# gm328a.net
KiCad netlist of a schematic drawn in EAGLE
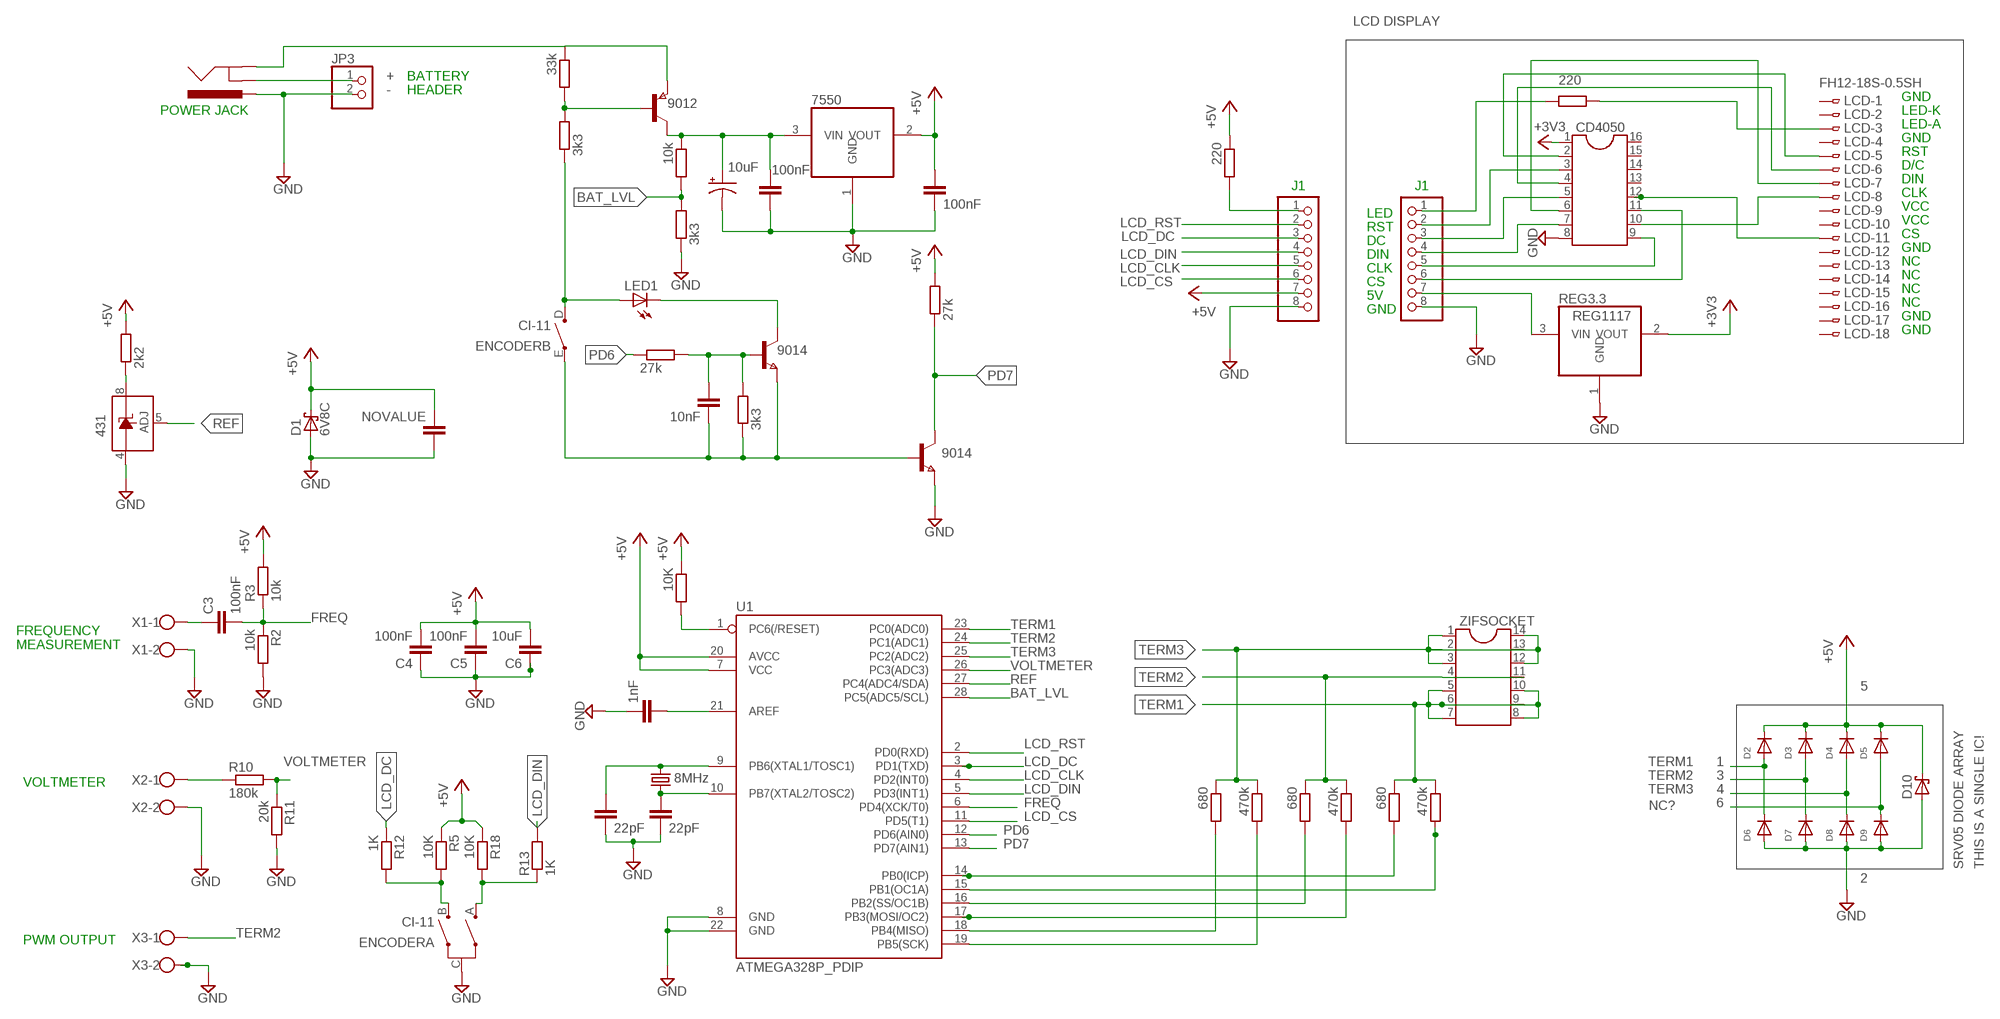
[diagram p0: schematic, sheet 1]

(export (version "E")
  (design (tool "Eeschema 10.0.6"))
  (components
    (comp (ref "1")
      (value "9014")
      (footprint "eagle-import:SOT323")
      (fields (field (name "MPN") "DSS4160U-7"))
      (libsource (lib "eagle-import") (part "NPNSOT323"))
    )
    (comp (ref "10K6")
      (value "10K")
      (footprint "eagle-import:M0805")
      (libsource (lib "eagle-import") (part "R-EU_M0805"))
    )
    (comp (ref "7550")
      (value "REG1117")
      (footprint "eagle-import:SOT223")
      (libsource (lib "eagle-import") (part "REG1117"))
    )
    (comp (ref "9012")
      (value "PNPSOT323")
      (footprint "eagle-import:SOT323")
      (fields (field (name "MPN") "2DB1689-7"))
      (libsource (lib "eagle-import") (part "PNPSOT323"))
    )
    (comp (ref "9014")
      (value "NPNSOT323")
      (footprint "eagle-import:SOT323")
      (fields (field (name "MPN") "DSS4160U-7"))
      (libsource (lib "eagle-import") (part "NPNSOT323"))
    )
    (comp (ref "C1")
      (value "22pF")
      (footprint "eagle-import:C0805")
      (libsource (lib "eagle-import") (part "C-EUC0805"))
    )
    (comp (ref "C2")
      (value "22pF")
      (footprint "eagle-import:C0805")
      (libsource (lib "eagle-import") (part "C-EUC0805"))
    )
    (comp (ref "C3")
      (value "100nF")
      (footprint "eagle-import:C0805")
      (libsource (lib "eagle-import") (part "C-EUC0805"))
    )
    (comp (ref "C4")
      (value "100nF")
      (footprint "eagle-import:C0805")
      (libsource (lib "eagle-import") (part "C-EUC0805"))
    )
    (comp (ref "C5")
      (value "100nF")
      (footprint "eagle-import:C0805")
      (libsource (lib "eagle-import") (part "C-EUC0805"))
    )
    (comp (ref "C6")
      (value "10uF")
      (footprint "eagle-import:C0805")
      (libsource (lib "eagle-import") (part "C-EUC0805"))
    )
    (comp (ref "C7")
      (value "100nF")
      (footprint "eagle-import:C0805")
      (libsource (lib "eagle-import") (part "C-EUC0805"))
    )
    (comp (ref "C8")
      (value "10uF")
      (footprint "eagle-import:PANASONIC_C")
      (libsource (lib "eagle-import") (part "CPOL-USC"))
    )
    (comp (ref "C9")
      (value "100nF")
      (footprint "eagle-import:C0805")
      (libsource (lib "eagle-import") (part "C-EUC0805"))
    )
    (comp (ref "C10")
      (value "10nF")
      (footprint "eagle-import:C0805")
      (libsource (lib "eagle-import") (part "C-EUC0805"))
    )
    (comp (ref "C11")
      (value "1nF")
      (footprint "eagle-import:C0805")
      (libsource (lib "eagle-import") (part "C-EUC0805"))
    )
    (comp (ref "C12")
      (value "NOVALUE")
      (footprint "eagle-import:C0805")
      (libsource (lib "eagle-import") (part "C-EUC0805"))
    )
    (comp (ref "CD4050")
      (value "DIL16")
      (footprint "eagle-import:DIL16")
      (libsource (lib "eagle-import") (part "DIL16"))
    )
    (comp (ref "D1")
      (value "6V8C")
      (footprint "eagle-import:DO41-10")
      (libsource (lib "eagle-import") (part "P4KEXX"))
    )
    (comp (ref "D2")
      (value "DIODE_SOD-123FL")
      (footprint "eagle-import:SOD-123FL")
      (libsource (lib "eagle-import") (part "DIODE_SOD-123FL"))
    )
    (comp (ref "D3")
      (value "DIODE_SOD-123FL")
      (footprint "eagle-import:SOD-123FL")
      (libsource (lib "eagle-import") (part "DIODE_SOD-123FL"))
    )
    (comp (ref "D4")
      (value "DIODE_SOD-123FL")
      (footprint "eagle-import:SOD-123FL")
      (libsource (lib "eagle-import") (part "DIODE_SOD-123FL"))
    )
    (comp (ref "D5")
      (value "DIODE_SOD-123FL")
      (footprint "eagle-import:SOD-123FL")
      (libsource (lib "eagle-import") (part "DIODE_SOD-123FL"))
    )
    (comp (ref "D6")
      (value "DIODE_SOD-123FL")
      (footprint "eagle-import:SOD-123FL")
      (libsource (lib "eagle-import") (part "DIODE_SOD-123FL"))
    )
    (comp (ref "D7")
      (value "DIODE_SOD-123FL")
      (footprint "eagle-import:SOD-123FL")
      (libsource (lib "eagle-import") (part "DIODE_SOD-123FL"))
    )
    (comp (ref "D8")
      (value "DIODE_SOD-123FL")
      (footprint "eagle-import:SOD-123FL")
      (libsource (lib "eagle-import") (part "DIODE_SOD-123FL"))
    )
    (comp (ref "D9")
      (value "DIODE_SOD-123FL")
      (footprint "eagle-import:SOD-123FL")
      (libsource (lib "eagle-import") (part "DIODE_SOD-123FL"))
    )
    (comp (ref "D10")
      (value "P4KEXX")
      (footprint "eagle-import:DO41-10")
      (libsource (lib "eagle-import") (part "P4KEXX"))
    )
    (comp (ref "ENCODER")
      (value "CI-11")
      (footprint "eagle-import:CI-11")
      (libsource (lib "eagle-import") (part "CI-11"))
    )
    (comp (ref "IC1")
      (value "LM336D")
      (footprint "eagle-import:SO08")
      (libsource (lib "eagle-import") (part "LM336D"))
    )
    (comp (ref "J1")
      (value "POWER_JACKSLT")
      (footprint "eagle-import:POWER_JACK_SLOT")
      (libsource (lib "eagle-import") (part "POWER_JACKSLT"))
    )
    (comp (ref "JP1")
      (value "PINHD-1X8")
      (footprint "eagle-import:1X08")
      (libsource (lib "eagle-import") (part "PINHD-1X8"))
    )
    (comp (ref "JP2")
      (value "PINHD-1X8")
      (footprint "eagle-import:1X08")
      (libsource (lib "eagle-import") (part "PINHD-1X8"))
    )
    (comp (ref "JP3")
      (value "PINHD-1X2")
      (footprint "eagle-import:1X02")
      (libsource (lib "eagle-import") (part "PINHD-1X2"))
    )
    (comp (ref "LCD")
      (value "FH12-18S-0.5SH")
      (footprint "eagle-import:FH12-18S-0.5SH")
      (fields (field (name "MPN") "FH12-18S-0.5SH(55)"))
      (libsource (lib "eagle-import") (part "FH12-18S-0.5SH"))
    )
    (comp (ref "LED1")
      (value "LEDSML0805")
      (footprint "eagle-import:SML0805")
      (libsource (lib "eagle-import") (part "LEDSML0805"))
    )
    (comp (ref "Q1")
      (value "8MHz")
      (footprint "eagle-import:HC49_S")
      (libsource (lib "eagle-import") (part "CRYSTALHC49S"))
    )
    (comp (ref "R1")
      (value "220")
      (footprint "eagle-import:M0805")
      (libsource (lib "eagle-import") (part "R-EU_M0805"))
    )
    (comp (ref "R2")
      (value "10k")
      (footprint "eagle-import:M0805")
      (libsource (lib "eagle-import") (part "R-EU_M0805"))
    )
    (comp (ref "R3")
      (value "10k")
      (footprint "eagle-import:M0805")
      (libsource (lib "eagle-import") (part "R-EU_M0805"))
    )
    (comp (ref "R4")
      (value "220")
      (footprint "eagle-import:M0805")
      (libsource (lib "eagle-import") (part "R-EU_M0805"))
    )
    (comp (ref "R5")
      (value "10K")
      (footprint "eagle-import:M0805")
      (libsource (lib "eagle-import") (part "R-EU_M0805"))
    )
    (comp (ref "R6")
      (value "33k")
      (footprint "eagle-import:M0805")
      (libsource (lib "eagle-import") (part "R-EU_M0805"))
    )
    (comp (ref "R7")
      (value "3k3")
      (footprint "eagle-import:M0805")
      (libsource (lib "eagle-import") (part "R-EU_M0805"))
    )
    (comp (ref "R8")
      (value "3k3")
      (footprint "eagle-import:M0805")
      (libsource (lib "eagle-import") (part "R-EU_M0805"))
    )
    (comp (ref "R9")
      (value "10k")
      (footprint "eagle-import:M0805")
      (libsource (lib "eagle-import") (part "R-EU_M0805"))
    )
    (comp (ref "R10")
      (value "180k")
      (footprint "eagle-import:M0805")
      (libsource (lib "eagle-import") (part "R-EU_M0805"))
    )
    (comp (ref "R11")
      (value "20k")
      (footprint "eagle-import:M0805")
      (libsource (lib "eagle-import") (part "R-EU_M0805"))
    )
    (comp (ref "R12")
      (value "1K")
      (footprint "eagle-import:M0805")
      (libsource (lib "eagle-import") (part "R-EU_M0805"))
    )
    (comp (ref "R13")
      (value "1K")
      (footprint "eagle-import:M0805")
      (libsource (lib "eagle-import") (part "R-EU_M0805"))
    )
    (comp (ref "R14")
      (value "2k2")
      (footprint "eagle-import:M0805")
      (libsource (lib "eagle-import") (part "R-EU_M0805"))
    )
    (comp (ref "R15")
      (value "27k")
      (footprint "eagle-import:M0805")
      (libsource (lib "eagle-import") (part "R-EU_M0805"))
    )
    (comp (ref "R16")
      (value "3k3")
      (footprint "eagle-import:M0805")
      (libsource (lib "eagle-import") (part "R-EU_M0805"))
    )
    (comp (ref "R17")
      (value "27k")
      (footprint "eagle-import:M0805")
      (libsource (lib "eagle-import") (part "R-EU_M0805"))
    )
    (comp (ref "R18")
      (value "10K")
      (footprint "eagle-import:M0805")
      (libsource (lib "eagle-import") (part "R-EU_M0805"))
    )
    (comp (ref "R19")
      (value "680")
      (footprint "eagle-import:M0805")
      (libsource (lib "eagle-import") (part "R-EU_M0805"))
    )
    (comp (ref "R20")
      (value "470k")
      (footprint "eagle-import:M0805")
      (libsource (lib "eagle-import") (part "R-EU_M0805"))
    )
    (comp (ref "R21")
      (value "680")
      (footprint "eagle-import:M0805")
      (libsource (lib "eagle-import") (part "R-EU_M0805"))
    )
    (comp (ref "R22")
      (value "470k")
      (footprint "eagle-import:M0805")
      (libsource (lib "eagle-import") (part "R-EU_M0805"))
    )
    (comp (ref "R23")
      (value "680")
      (footprint "eagle-import:M0805")
      (libsource (lib "eagle-import") (part "R-EU_M0805"))
    )
    (comp (ref "R24")
      (value "470k")
      (footprint "eagle-import:M0805")
      (libsource (lib "eagle-import") (part "R-EU_M0805"))
    )
    (comp (ref "REG3.3")
      (value "REG1117")
      (footprint "eagle-import:SOT223")
      (libsource (lib "eagle-import") (part "REG1117"))
    )
    (comp (ref "U1")
      (value "ATMEGA328P_PDIP")
      (footprint "eagle-import:DIL28-3")
      (libsource (lib "eagle-import") (part "ATMEGA328P_PDIP"))
    )
    (comp (ref "X1")
      (value "W237-102")
      (footprint "eagle-import:W237-102")
      (fields (field (name "MPN") "237-102"))
      (libsource (lib "eagle-import") (part "W237-102"))
    )
    (comp (ref "X2")
      (value "W237-102")
      (footprint "eagle-import:W237-102")
      (fields (field (name "MPN") "237-102"))
      (libsource (lib "eagle-import") (part "W237-102"))
    )
    (comp (ref "X3")
      (value "W237-102")
      (footprint "eagle-import:W237-102")
      (fields (field (name "MPN") "237-102"))
      (libsource (lib "eagle-import") (part "W237-102"))
    )
    (comp (ref "ZIFSOCKET")
      (value "DIL14S")
      (footprint "eagle-import:SOCKET-14")
      (libsource (lib "eagle-import") (part "DIL14S"))
    )
  )
  (nets
    (net (code "1") (name "+3V3") (class "Default")
      (node (ref "CD4050") (pin "1") (pinfunction "1_1") (pintype "passive"))
      (node (ref "REG3.3") (pin "2") (pinfunction "VOUT_2") (pintype "output"))
    )
    (net (code "2") (name "+5V") (class "Default")
      (node (ref "10K6") (pin "1") (pinfunction "1_1") (pintype "passive"))
      (node (ref "7550") (pin "2") (pinfunction "VOUT_2") (pintype "output"))
      (node (ref "C12") (pin "2") (pinfunction "2_2") (pintype "passive"))
      (node (ref "C4") (pin "2") (pinfunction "2_2") (pintype "passive"))
      (node (ref "C5") (pin "2") (pinfunction "2_2") (pintype "passive"))
      (node (ref "C6") (pin "2") (pinfunction "2_2") (pintype "passive"))
      (node (ref "C9") (pin "1") (pinfunction "1_1") (pintype "passive"))
      (node (ref "D1") (pin "C") (pinfunction "C_C") (pintype "passive"))
      (node (ref "D10") (pin "C") (pinfunction "C_C") (pintype "passive"))
      (node (ref "D2") (pin "C") (pinfunction "C_C") (pintype "passive"))
      (node (ref "D3") (pin "C") (pinfunction "C_C") (pintype "passive"))
      (node (ref "D4") (pin "C") (pinfunction "C_C") (pintype "passive"))
      (node (ref "D5") (pin "C") (pinfunction "C_C") (pintype "passive"))
      (node (ref "JP1") (pin "7") (pinfunction "7_7") (pintype "passive"))
      (node (ref "R14") (pin "2") (pinfunction "2_2") (pintype "passive"))
      (node (ref "R17") (pin "2") (pinfunction "2_2") (pintype "passive"))
      (node (ref "R18") (pin "1") (pinfunction "1_1") (pintype "passive"))
      (node (ref "R3") (pin "2") (pinfunction "2_2") (pintype "passive"))
      (node (ref "R4") (pin "1") (pinfunction "1_1") (pintype "passive"))
      (node (ref "R5") (pin "1") (pinfunction "1_1") (pintype "passive"))
      (node (ref "U1") (pin "20") (pinfunction "AVCC_20") (pintype "bidirectional"))
      (node (ref "U1") (pin "7") (pinfunction "VCC_7") (pintype "bidirectional"))
    )
    (net (code "3") (name "/FREQ") (class "Default")
      (node (ref "C3") (pin "2") (pinfunction "2_2") (pintype "passive"))
      (node (ref "R2") (pin "1") (pinfunction "1_1") (pintype "passive"))
      (node (ref "R3") (pin "1") (pinfunction "1_1") (pintype "passive"))
      (node (ref "U1") (pin "6") (pinfunction "PD4(XCK/T0)_6") (pintype "bidirectional"))
    )
    (net (code "4") (name "/LCD_CLK") (class "Default")
      (node (ref "JP1") (pin "5") (pinfunction "5_5") (pintype "passive"))
      (node (ref "U1") (pin "4") (pinfunction "PD2(INT0)_4") (pintype "bidirectional"))
    )
    (net (code "5") (name "/LCD_CS") (class "Default")
      (node (ref "JP1") (pin "6") (pinfunction "6_6") (pintype "passive"))
      (node (ref "U1") (pin "11") (pinfunction "PD5(T1)_11") (pintype "bidirectional"))
    )
    (net (code "6") (name "/LCD_RST") (class "Default")
      (node (ref "JP1") (pin "2") (pinfunction "2_2") (pintype "passive"))
      (node (ref "U1") (pin "2") (pinfunction "PD0(RXD)_2") (pintype "bidirectional"))
    )
    (net (code "7") (name "/NC?") (class "Default")
      (node (ref "D5") (pin "A") (pinfunction "A_A") (pintype "passive"))
      (node (ref "D9") (pin "C") (pinfunction "C_C") (pintype "passive"))
    )
    (net (code "8") (name "/VOLTMETER") (class "Default")
      (node (ref "R10") (pin "2") (pinfunction "2_2") (pintype "passive"))
      (node (ref "R11") (pin "1") (pinfunction "1_1") (pintype "passive"))
      (node (ref "U1") (pin "26") (pinfunction "PC3(ADC3)_26") (pintype "bidirectional"))
    )
    (net (code "9") (name "BAT_LVL") (class "Default")
      (node (ref "R8") (pin "2") (pinfunction "2_2") (pintype "passive"))
      (node (ref "R9") (pin "2") (pinfunction "2_2") (pintype "passive"))
      (node (ref "U1") (pin "28") (pinfunction "PC5(ADC5/SCL)_28") (pintype "bidirectional"))
    )
    (net (code "10") (name "GND") (class "Default")
      (node (ref "7550") (pin "1") (pinfunction "GND_1") (pintype "power_in"))
      (node (ref "9014") (pin "3") (pinfunction "E_3") (pintype "passive"))
      (node (ref "C1") (pin "2") (pinfunction "2_2") (pintype "passive"))
      (node (ref "C11") (pin "1") (pinfunction "1_1") (pintype "passive"))
      (node (ref "C12") (pin "1") (pinfunction "1_1") (pintype "passive"))
      (node (ref "C2") (pin "2") (pinfunction "2_2") (pintype "passive"))
      (node (ref "C4") (pin "1") (pinfunction "1_1") (pintype "passive"))
      (node (ref "C5") (pin "1") (pinfunction "1_1") (pintype "passive"))
      (node (ref "C6") (pin "1") (pinfunction "1_1") (pintype "passive"))
      (node (ref "C7") (pin "2") (pinfunction "2_2") (pintype "passive"))
      (node (ref "C8") (pin "-") (pinfunction "-_-") (pintype "passive"))
      (node (ref "C9") (pin "2") (pinfunction "2_2") (pintype "passive"))
      (node (ref "CD4050") (pin "8") (pinfunction "8_8") (pintype "passive"))
      (node (ref "D1") (pin "A") (pinfunction "A_A") (pintype "passive"))
      (node (ref "D10") (pin "A") (pinfunction "A_A") (pintype "passive"))
      (node (ref "D6") (pin "A") (pinfunction "A_A") (pintype "passive"))
      (node (ref "D7") (pin "A") (pinfunction "A_A") (pintype "passive"))
      (node (ref "D8") (pin "A") (pinfunction "A_A") (pintype "passive"))
      (node (ref "D9") (pin "A") (pinfunction "A_A") (pintype "passive"))
      (node (ref "ENCODER") (pin "C") (pinfunction "C_C") (pintype "passive"))
      (node (ref "IC1") (pin "4") (pinfunction "A_4") (pintype "input"))
      (node (ref "J1") (pin "PWR") (pinfunction "PWR_PWR") (pintype "bidirectional"))
      (node (ref "JP1") (pin "8") (pinfunction "8_8") (pintype "passive"))
      (node (ref "JP2") (pin "8") (pinfunction "8_8") (pintype "passive"))
      (node (ref "JP3") (pin "2") (pinfunction "2_2") (pintype "passive"))
      (node (ref "R11") (pin "2") (pinfunction "2_2") (pintype "passive"))
      (node (ref "R2") (pin "2") (pinfunction "2_2") (pintype "passive"))
      (node (ref "R8") (pin "1") (pinfunction "1_1") (pintype "passive"))
      (node (ref "REG3.3") (pin "1") (pinfunction "GND_1") (pintype "power_in"))
      (node (ref "U1") (pin "22") (pinfunction "GND_22") (pintype "bidirectional"))
      (node (ref "U1") (pin "8") (pinfunction "GND_8") (pintype "bidirectional"))
      (node (ref "X1") (pin "2") (pinfunction "KL_2") (pintype "passive"))
      (node (ref "X2") (pin "2") (pinfunction "KL_2") (pintype "passive"))
      (node (ref "X3") (pin "2") (pinfunction "KL_2") (pintype "passive"))
    )
    (net (code "11") (name "LCD_DC") (class "Default")
      (node (ref "JP1") (pin "3") (pinfunction "3_3") (pintype "passive"))
      (node (ref "R12") (pin "1") (pinfunction "1_1") (pintype "passive"))
      (node (ref "U1") (pin "3") (pinfunction "PD1(TXD)_3") (pintype "bidirectional"))
    )
    (net (code "12") (name "LCD_DIN") (class "Default")
      (node (ref "JP1") (pin "4") (pinfunction "4_4") (pintype "passive"))
      (node (ref "R13") (pin "2") (pinfunction "2_2") (pintype "passive"))
      (node (ref "U1") (pin "5") (pinfunction "PD3(INT1)_5") (pintype "bidirectional"))
    )
    (net (code "13") (name "Net-(1-B)") (class "Default")
      (node (ref "1") (pin "2") (pinfunction "B_2") (pintype "passive"))
      (node (ref "C10") (pin "2") (pinfunction "2_2") (pintype "passive"))
      (node (ref "R15") (pin "2") (pinfunction "2_2") (pintype "passive"))
      (node (ref "R16") (pin "2") (pinfunction "2_2") (pintype "passive"))
    )
    (net (code "14") (name "Net-(1-C)") (class "Default")
      (node (ref "1") (pin "1") (pinfunction "C_1") (pintype "passive"))
      (node (ref "LED1") (pin "C") (pinfunction "C_C") (pintype "passive"))
    )
    (net (code "15") (name "Net-(1-E)") (class "Default")
      (node (ref "1") (pin "3") (pinfunction "E_3") (pintype "passive"))
      (node (ref "9014") (pin "2") (pinfunction "B_2") (pintype "passive"))
      (node (ref "C10") (pin "1") (pinfunction "1_1") (pintype "passive"))
      (node (ref "ENCODER") (pin "E") (pinfunction "E_E") (pintype "passive"))
      (node (ref "R16") (pin "1") (pinfunction "1_1") (pintype "passive"))
    )
    (net (code "16") (name "Net-(7550-VIN)") (class "Default")
      (node (ref "7550") (pin "3") (pinfunction "VIN_3") (pintype "input"))
      (node (ref "9012") (pin "1") (pinfunction "C_1") (pintype "passive"))
      (node (ref "C7") (pin "1") (pinfunction "1_1") (pintype "passive"))
      (node (ref "C8") (pin "+") (pinfunction "+_+") (pintype "passive"))
      (node (ref "R9") (pin "1") (pinfunction "1_1") (pintype "passive"))
    )
    (net (code "17") (name "Net-(9012-B)") (class "Default")
      (node (ref "9012") (pin "2") (pinfunction "B_2") (pintype "passive"))
      (node (ref "R6") (pin "2") (pinfunction "2_2") (pintype "passive"))
      (node (ref "R7") (pin "2") (pinfunction "2_2") (pintype "passive"))
    )
    (net (code "18") (name "Net-(9012-E)") (class "Default")
      (node (ref "9012") (pin "3") (pinfunction "E_3") (pintype "passive"))
      (node (ref "J1") (pin "GND@2") (pinfunction "GND_GND@2") (pintype "bidirectional"))
      (node (ref "R6") (pin "1") (pinfunction "1_1") (pintype "passive"))
    )
    (net (code "19") (name "Net-(CD4050-Pad3)") (class "Default")
      (node (ref "CD4050") (pin "3") (pinfunction "3_3") (pintype "passive"))
      (node (ref "JP2") (pin "2") (pinfunction "2_2") (pintype "passive"))
    )
    (net (code "20") (name "Net-(CD4050-Pad5)") (class "Default")
      (node (ref "CD4050") (pin "5") (pinfunction "5_5") (pintype "passive"))
      (node (ref "JP2") (pin "3") (pinfunction "3_3") (pintype "passive"))
    )
    (net (code "21") (name "Net-(CD4050-Pad7)") (class "Default")
      (node (ref "CD4050") (pin "7") (pinfunction "7_7") (pintype "passive"))
      (node (ref "JP2") (pin "4") (pinfunction "4_4") (pintype "passive"))
    )
    (net (code "22") (name "Net-(CD4050-Pad9)") (class "Default")
      (node (ref "CD4050") (pin "9") (pinfunction "9_9") (pintype "passive"))
      (node (ref "JP2") (pin "5") (pinfunction "5_5") (pintype "passive"))
    )
    (net (code "23") (name "Net-(CD4050-Pad11)") (class "Default")
      (node (ref "CD4050") (pin "11") (pinfunction "11_11") (pintype "passive"))
      (node (ref "JP2") (pin "6") (pinfunction "6_6") (pintype "passive"))
    )
    (net (code "24") (name "Net-(ENCODER-PadA)") (class "Default")
      (node (ref "ENCODER") (pin "A") (pinfunction "A_A") (pintype "passive"))
      (node (ref "R13") (pin "1") (pinfunction "1_1") (pintype "passive"))
      (node (ref "R18") (pin "2") (pinfunction "2_2") (pintype "passive"))
    )
    (net (code "25") (name "Net-(ENCODER-PadB)") (class "Default")
      (node (ref "ENCODER") (pin "B") (pinfunction "B_B") (pintype "passive"))
      (node (ref "R12") (pin "2") (pinfunction "2_2") (pintype "passive"))
      (node (ref "R5") (pin "2") (pinfunction "2_2") (pintype "passive"))
    )
    (net (code "26") (name "Net-(ENCODER-PadD)") (class "Default")
      (node (ref "ENCODER") (pin "D") (pinfunction "D_D") (pintype "passive"))
      (node (ref "LED1") (pin "A") (pinfunction "A_A") (pintype "passive"))
      (node (ref "R7") (pin "1") (pinfunction "1_1") (pintype "passive"))
    )
    (net (code "27") (name "Net-(IC1-C)") (class "Default")
      (node (ref "IC1") (pin "8") (pinfunction "C_8") (pintype "passive"))
      (node (ref "R14") (pin "1") (pinfunction "1_1") (pintype "passive"))
    )
    (net (code "28") (name "Net-(J1-GNDBREAK)") (class "Default")
      (node (ref "J1") (pin "GND@1") (pinfunction "GNDBREAK_GND@1") (pintype "bidirectional"))
      (node (ref "JP3") (pin "1") (pinfunction "1_1") (pintype "passive"))
    )
    (net (code "29") (name "Net-(JP1-Pad1)") (class "Default")
      (node (ref "JP1") (pin "1") (pinfunction "1_1") (pintype "passive"))
      (node (ref "R4") (pin "2") (pinfunction "2_2") (pintype "passive"))
    )
    (net (code "30") (name "Net-(JP2-Pad1)") (class "Default")
      (node (ref "JP2") (pin "1") (pinfunction "1_1") (pintype "passive"))
      (node (ref "R1") (pin "1") (pinfunction "1_1") (pintype "passive"))
    )
    (net (code "31") (name "Net-(LCDC-1)") (class "Default")
      (node (ref "CD4050") (pin "12") (pinfunction "12_12") (pintype "passive"))
      (node (ref "LCD") (pin "11") (pinfunction "1_11") (pintype "passive"))
    )
    (net (code "32") (name "Net-(LCDL-1)") (class "Default")
      (node (ref "LCD") (pin "3") (pinfunction "1_3") (pintype "passive"))
      (node (ref "R1") (pin "2") (pinfunction "2_2") (pintype "passive"))
    )
    (net (code "33") (name "Net-(LCDN-1)") (class "Default")
      (node (ref "CD4050") (pin "2") (pinfunction "2_2") (pintype "passive"))
      (node (ref "LCD") (pin "5") (pinfunction "1_5") (pintype "passive"))
    )
    (net (code "34") (name "Net-(LCDO-1)") (class "Default")
      (node (ref "CD4050") (pin "4") (pinfunction "4_4") (pintype "passive"))
      (node (ref "LCD") (pin "6") (pinfunction "1_6") (pintype "passive"))
    )
    (net (code "35") (name "Net-(LCDP-1)") (class "Default")
      (node (ref "CD4050") (pin "6") (pinfunction "6_6") (pintype "passive"))
      (node (ref "LCD") (pin "7") (pinfunction "1_7") (pintype "passive"))
    )
    (net (code "36") (name "Net-(LCDQ-1)") (class "Default")
      (node (ref "CD4050") (pin "10") (pinfunction "10_10") (pintype "passive"))
      (node (ref "LCD") (pin "8") (pinfunction "1_8") (pintype "passive"))
    )
    (net (code "37") (name "Net-(REG3.3-VIN)") (class "Default")
      (node (ref "JP2") (pin "7") (pinfunction "7_7") (pintype "passive"))
      (node (ref "REG3.3") (pin "3") (pinfunction "VIN_3") (pintype "input"))
    )
    (net (code "38") (name "Net-(U1-AREF)") (class "Default")
      (node (ref "C11") (pin "2") (pinfunction "2_2") (pintype "passive"))
      (node (ref "U1") (pin "21") (pinfunction "AREF_21") (pintype "bidirectional"))
    )
    (net (code "39") (name "Net-(U1-PB0(ICP))") (class "Default")
      (node (ref "R23") (pin "2") (pinfunction "2_2") (pintype "passive"))
      (node (ref "U1") (pin "14") (pinfunction "PB0(ICP)_14") (pintype "bidirectional"))
    )
    (net (code "40") (name "Net-(U1-PB1(OC1A))") (class "Default")
      (node (ref "R24") (pin "2") (pinfunction "2_2") (pintype "passive"))
      (node (ref "U1") (pin "15") (pinfunction "PB1(OC1A)_15") (pintype "bidirectional"))
    )
    (net (code "41") (name "Net-(U1-PB2(SS{slash}OC1B))") (class "Default")
      (node (ref "R21") (pin "2") (pinfunction "2_2") (pintype "passive"))
      (node (ref "U1") (pin "16") (pinfunction "PB2(SS/OC1B)_16") (pintype "bidirectional"))
    )
    (net (code "42") (name "Net-(U1-PB3(MOSI{slash}OC2))") (class "Default")
      (node (ref "R22") (pin "2") (pinfunction "2_2") (pintype "passive"))
      (node (ref "U1") (pin "17") (pinfunction "PB3(MOSI/OC2)_17") (pintype "bidirectional"))
    )
    (net (code "43") (name "Net-(U1-PB4(MISO))") (class "Default")
      (node (ref "R19") (pin "2") (pinfunction "2_2") (pintype "passive"))
      (node (ref "U1") (pin "18") (pinfunction "PB4(MISO)_18") (pintype "bidirectional"))
    )
    (net (code "44") (name "Net-(U1-PB5(SCK))") (class "Default")
      (node (ref "R20") (pin "2") (pinfunction "2_2") (pintype "passive"))
      (node (ref "U1") (pin "19") (pinfunction "PB5(SCK)_19") (pintype "bidirectional"))
    )
    (net (code "45") (name "Net-(U1-PB6(XTAL1{slash}TOSC1))") (class "Default")
      (node (ref "C2") (pin "1") (pinfunction "1_1") (pintype "passive"))
      (node (ref "Q1") (pin "2") (pinfunction "2_2") (pintype "passive"))
      (node (ref "U1") (pin "9") (pinfunction "PB6(XTAL1/TOSC1)_9") (pintype "bidirectional"))
    )
    (net (code "46") (name "Net-(U1-PB7(XTAL2{slash}TOSC2))") (class "Default")
      (node (ref "C1") (pin "1") (pinfunction "1_1") (pintype "passive"))
      (node (ref "Q1") (pin "1") (pinfunction "1_1") (pintype "passive"))
      (node (ref "U1") (pin "10") (pinfunction "PB7(XTAL2/TOSC2)_10") (pintype "bidirectional"))
    )
    (net (code "47") (name "Net-(U1-PC6({slash}RESET))") (class "Default")
      (node (ref "10K6") (pin "2") (pinfunction "2_2") (pintype "passive"))
      (node (ref "U1") (pin "1") (pinfunction "PC6(/RESET)_1") (pintype "bidirectional"))
    )
    (net (code "48") (name "Net-(X1A-KL)") (class "Default")
      (node (ref "C3") (pin "1") (pinfunction "1_1") (pintype "passive"))
      (node (ref "X1") (pin "1") (pinfunction "KL_1") (pintype "passive"))
    )
    (net (code "49") (name "Net-(X2A-KL)") (class "Default")
      (node (ref "R10") (pin "1") (pinfunction "1_1") (pintype "passive"))
      (node (ref "X2") (pin "1") (pinfunction "KL_1") (pintype "passive"))
    )
    (net (code "50") (name "PD6") (class "Default")
      (node (ref "R15") (pin "1") (pinfunction "1_1") (pintype "passive"))
      (node (ref "U1") (pin "12") (pinfunction "PD6(AIN0)_12") (pintype "bidirectional"))
    )
    (net (code "51") (name "PD7") (class "Default")
      (node (ref "9014") (pin "1") (pinfunction "C_1") (pintype "passive"))
      (node (ref "R17") (pin "1") (pinfunction "1_1") (pintype "passive"))
      (node (ref "U1") (pin "13") (pinfunction "PD7(AIN1)_13") (pintype "bidirectional"))
    )
    (net (code "52") (name "REF") (class "Default")
      (node (ref "IC1") (pin "5") (pinfunction "ADJ_5") (pintype "input"))
      (node (ref "U1") (pin "27") (pinfunction "PC4(ADC4/SDA)_27") (pintype "bidirectional"))
    )
    (net (code "53") (name "TERM1") (class "Default")
      (node (ref "D2") (pin "A") (pinfunction "A_A") (pintype "passive"))
      (node (ref "D6") (pin "C") (pinfunction "C_C") (pintype "passive"))
      (node (ref "R23") (pin "1") (pinfunction "1_1") (pintype "passive"))
      (node (ref "R24") (pin "1") (pinfunction "1_1") (pintype "passive"))
      (node (ref "U1") (pin "23") (pinfunction "PC0(ADC0)_23") (pintype "bidirectional"))
      (node (ref "ZIFSOCKET") (pin "10") (pinfunction "10_10") (pintype "passive"))
      (node (ref "ZIFSOCKET") (pin "5") (pinfunction "5_5") (pintype "passive"))
      (node (ref "ZIFSOCKET") (pin "6") (pinfunction "6_6") (pintype "passive"))
      (node (ref "ZIFSOCKET") (pin "7") (pinfunction "7_7") (pintype "passive"))
      (node (ref "ZIFSOCKET") (pin "8") (pinfunction "8_8") (pintype "passive"))
      (node (ref "ZIFSOCKET") (pin "9") (pinfunction "9_9") (pintype "passive"))
    )
    (net (code "54") (name "TERM2") (class "Default")
      (node (ref "D3") (pin "A") (pinfunction "A_A") (pintype "passive"))
      (node (ref "D7") (pin "C") (pinfunction "C_C") (pintype "passive"))
      (node (ref "R21") (pin "1") (pinfunction "1_1") (pintype "passive"))
      (node (ref "R22") (pin "1") (pinfunction "1_1") (pintype "passive"))
      (node (ref "U1") (pin "24") (pinfunction "PC1(ADC1)_24") (pintype "bidirectional"))
      (node (ref "X3") (pin "1") (pinfunction "KL_1") (pintype "passive"))
      (node (ref "ZIFSOCKET") (pin "11") (pinfunction "11_11") (pintype "passive"))
      (node (ref "ZIFSOCKET") (pin "4") (pinfunction "4_4") (pintype "passive"))
    )
    (net (code "55") (name "TERM3") (class "Default")
      (node (ref "D4") (pin "A") (pinfunction "A_A") (pintype "passive"))
      (node (ref "D8") (pin "C") (pinfunction "C_C") (pintype "passive"))
      (node (ref "R19") (pin "1") (pinfunction "1_1") (pintype "passive"))
      (node (ref "R20") (pin "1") (pinfunction "1_1") (pintype "passive"))
      (node (ref "U1") (pin "25") (pinfunction "PC2(ADC2)_25") (pintype "bidirectional"))
      (node (ref "ZIFSOCKET") (pin "1") (pinfunction "1_1") (pintype "passive"))
      (node (ref "ZIFSOCKET") (pin "12") (pinfunction "12_12") (pintype "passive"))
      (node (ref "ZIFSOCKET") (pin "13") (pinfunction "13_13") (pintype "passive"))
      (node (ref "ZIFSOCKET") (pin "14") (pinfunction "14_14") (pintype "passive"))
      (node (ref "ZIFSOCKET") (pin "2") (pinfunction "2_2") (pintype "passive"))
      (node (ref "ZIFSOCKET") (pin "3") (pinfunction "3_3") (pintype "passive"))
    )
    (net (code "56") (name "unconnected-(CD4050-Pad13)") (class "Default")
      (node (ref "CD4050") (pin "13") (pinfunction "13_13") (pintype "passive"))
    )
    (net (code "57") (name "unconnected-(CD4050-Pad14)") (class "Default")
      (node (ref "CD4050") (pin "14") (pinfunction "14_14") (pintype "passive"))
    )
    (net (code "58") (name "unconnected-(CD4050-Pad15)") (class "Default")
      (node (ref "CD4050") (pin "15") (pinfunction "15_15") (pintype "passive"))
    )
    (net (code "59") (name "unconnected-(CD4050-Pad16)") (class "Default")
      (node (ref "CD4050") (pin "16") (pinfunction "16_16") (pintype "passive"))
    )
    (net (code "60") (name "unconnected-(LCD-Pad1)") (class "Default")
      (node (ref "LCD") (pin "1") (pinfunction "1_1") (pintype "passive"))
    )
    (net (code "61") (name "unconnected-(LCDB-1-Pad10)") (class "Default")
      (node (ref "LCD") (pin "10") (pinfunction "1_10") (pintype "passive"))
    )
    (net (code "62") (name "unconnected-(LCDD-1-Pad12)") (class "Default")
      (node (ref "LCD") (pin "12") (pinfunction "1_12") (pintype "passive"))
    )
    (net (code "63") (name "unconnected-(LCDE-1-Pad13)") (class "Default")
      (node (ref "LCD") (pin "13") (pinfunction "1_13") (pintype "passive"))
    )
    (net (code "64") (name "unconnected-(LCDF-1-Pad14)") (class "Default")
      (node (ref "LCD") (pin "14") (pinfunction "1_14") (pintype "passive"))
    )
    (net (code "65") (name "unconnected-(LCDG-1-Pad15)") (class "Default")
      (node (ref "LCD") (pin "15") (pinfunction "1_15") (pintype "passive"))
    )
    (net (code "66") (name "unconnected-(LCDH-1-Pad16)") (class "Default")
      (node (ref "LCD") (pin "16") (pinfunction "1_16") (pintype "passive"))
    )
    (net (code "67") (name "unconnected-(LCDI-1-Pad17)") (class "Default")
      (node (ref "LCD") (pin "17") (pinfunction "1_17") (pintype "passive"))
    )
    (net (code "68") (name "unconnected-(LCDJ-1-Pad18)") (class "Default")
      (node (ref "LCD") (pin "18") (pinfunction "1_18") (pintype "passive"))
    )
    (net (code "69") (name "unconnected-(LCDK-1-Pad2)") (class "Default")
      (node (ref "LCD") (pin "2") (pinfunction "1_2") (pintype "passive"))
    )
    (net (code "70") (name "unconnected-(LCDM-1-Pad4)") (class "Default")
      (node (ref "LCD") (pin "4") (pinfunction "1_4") (pintype "passive"))
    )
    (net (code "71") (name "unconnected-(LCDR-1-Pad9)") (class "Default")
      (node (ref "LCD") (pin "9") (pinfunction "1_9") (pintype "passive"))
    )
  )
)
